# RS232_NPN_PNP_FTDI232.net
KiCad netlist of a schematic drawn in EAGLE
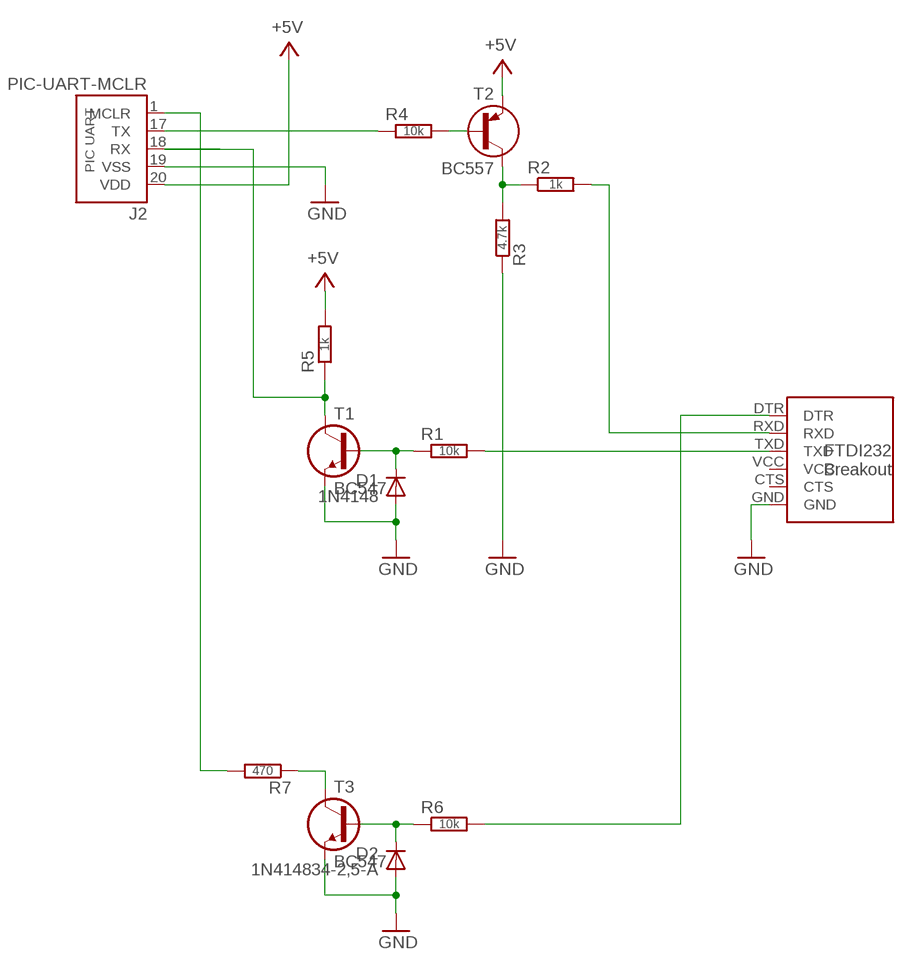
[diagram p0: schematic, sheet 1]

(export (version "E")
  (design (tool "Eeschema 10.0.6"))
  (components
    (comp (ref "D1")
      (value "1N4148")
      (footprint "eagle-import:DO34-5")
      (libsource (lib "eagle-import") (part "1N414834-5"))
    )
    (comp (ref "D2")
      (value "1N414834-2,5-A")
      (footprint "eagle-import:DO34-2,5-A")
      (libsource (lib "eagle-import") (part "1N414834-2,5-A"))
    )
    (comp (ref "J1")
      (value "FTDI232-BO-R")
      (footprint "eagle-import:FTDI232-BO-L")
      (libsource (lib "eagle-import") (part "FTDI232-BO-R"))
    )
    (comp (ref "J2")
      (value "PIC-UART-MCLR")
      (footprint "eagle-import:PIC-UART-MCLR")
      (libsource (lib "eagle-import") (part "PIC-UART-MCLR"))
    )
    (comp (ref "R1")
      (value "10k")
      (footprint "eagle-import:0202_5")
      (libsource (lib "eagle-import") (part "R0202/5"))
    )
    (comp (ref "R2")
      (value "1k")
      (footprint "eagle-import:0202_10")
      (libsource (lib "eagle-import") (part "R0202/10"))
    )
    (comp (ref "R3")
      (value "4.7k")
      (footprint "eagle-import:0202_5")
      (libsource (lib "eagle-import") (part "R0202/5"))
    )
    (comp (ref "R4")
      (value "10k")
      (footprint "eagle-import:0202_7-V")
      (libsource (lib "eagle-import") (part "R0202/7-V"))
    )
    (comp (ref "R5")
      (value "1k")
      (footprint "eagle-import:0202_5-V")
      (libsource (lib "eagle-import") (part "R0202/5-V"))
    )
    (comp (ref "R6")
      (value "10k")
      (footprint "eagle-import:0202_7-V")
      (libsource (lib "eagle-import") (part "R0202/7-V"))
    )
    (comp (ref "R7")
      (value "470")
      (footprint "eagle-import:0202_7-V")
      (libsource (lib "eagle-import") (part "R0202/7-V"))
    )
    (comp (ref "T1")
      (value "BC547")
      (footprint "eagle-import:TO92-CBE")
      (libsource (lib "eagle-import") (part "BC547CBE"))
    )
    (comp (ref "T2")
      (value "BC557")
      (footprint "eagle-import:TO92-CBE")
      (libsource (lib "eagle-import") (part "BC557CBE"))
    )
    (comp (ref "T3")
      (value "BC547")
      (footprint "eagle-import:TO92-CBE")
      (libsource (lib "eagle-import") (part "BC547CBE"))
    )
  )
  (nets
    (net (code "1") (name "+5V") (class "Default")
      (node (ref "J2") (pin "20") (pinfunction "VDD_20") (pintype "passive"))
      (node (ref "R5") (pin "2") (pinfunction "2_2") (pintype "passive"))
      (node (ref "T2") (pin "E") (pinfunction "E_E") (pintype "passive"))
    )
    (net (code "2") (name "GND") (class "Default")
      (node (ref "D1") (pin "A") (pinfunction "A_A") (pintype "passive"))
      (node (ref "D2") (pin "A") (pinfunction "A_A") (pintype "passive"))
      (node (ref "J1") (pin "GND") (pinfunction "GND_GND") (pintype "bidirectional"))
      (node (ref "J2") (pin "19") (pinfunction "VSS_19") (pintype "passive"))
      (node (ref "R3") (pin "1") (pinfunction "1_1") (pintype "passive"))
      (node (ref "T1") (pin "E") (pinfunction "E_E") (pintype "passive"))
      (node (ref "T3") (pin "E") (pinfunction "E_E") (pintype "passive"))
    )
    (net (code "3") (name "Net-(D1-PadC)") (class "Default")
      (node (ref "D1") (pin "C") (pinfunction "C_C") (pintype "passive"))
      (node (ref "R1") (pin "1") (pinfunction "1_1") (pintype "passive"))
      (node (ref "T1") (pin "B") (pinfunction "B_B") (pintype "passive"))
    )
    (net (code "4") (name "Net-(D2-PadC)") (class "Default")
      (node (ref "D2") (pin "C") (pinfunction "C_C") (pintype "passive"))
      (node (ref "R6") (pin "1") (pinfunction "1_1") (pintype "passive"))
      (node (ref "T3") (pin "B") (pinfunction "B_B") (pintype "passive"))
    )
    (net (code "5") (name "Net-(J1-PadDTR)") (class "Default")
      (node (ref "J1") (pin "DTR") (pinfunction "DTR_DTR") (pintype "bidirectional"))
      (node (ref "R6") (pin "2") (pinfunction "2_2") (pintype "passive"))
    )
    (net (code "6") (name "Net-(J1-PadRXD)") (class "Default")
      (node (ref "J1") (pin "RXD") (pinfunction "RXD_RXD") (pintype "bidirectional"))
      (node (ref "R2") (pin "2") (pinfunction "2_2") (pintype "passive"))
    )
    (net (code "7") (name "Net-(J1-PadTXD)") (class "Default")
      (node (ref "J1") (pin "TXD") (pinfunction "TXD_TXD") (pintype "bidirectional"))
      (node (ref "R1") (pin "2") (pinfunction "2_2") (pintype "passive"))
    )
    (net (code "8") (name "Net-(J2-MCLR)") (class "Default")
      (node (ref "J2") (pin "1") (pinfunction "MCLR_1") (pintype "passive"))
      (node (ref "R7") (pin "2") (pinfunction "2_2") (pintype "passive"))
    )
    (net (code "9") (name "Net-(J2-RX)") (class "Default")
      (node (ref "J2") (pin "18") (pinfunction "RX_18") (pintype "passive"))
      (node (ref "R5") (pin "1") (pinfunction "1_1") (pintype "passive"))
      (node (ref "T1") (pin "C") (pinfunction "C_C") (pintype "passive"))
    )
    (net (code "10") (name "Net-(J2-TX)") (class "Default")
      (node (ref "J2") (pin "17") (pinfunction "TX_17") (pintype "passive"))
      (node (ref "R4") (pin "1") (pinfunction "1_1") (pintype "passive"))
    )
    (net (code "11") (name "Net-(R2-Pad1)") (class "Default")
      (node (ref "R2") (pin "1") (pinfunction "1_1") (pintype "passive"))
      (node (ref "R3") (pin "2") (pinfunction "2_2") (pintype "passive"))
      (node (ref "T2") (pin "C") (pinfunction "C_C") (pintype "passive"))
    )
    (net (code "12") (name "Net-(R4-Pad2)") (class "Default")
      (node (ref "R4") (pin "2") (pinfunction "2_2") (pintype "passive"))
      (node (ref "T2") (pin "B") (pinfunction "B_B") (pintype "passive"))
    )
    (net (code "13") (name "Net-(R7-Pad1)") (class "Default")
      (node (ref "R7") (pin "1") (pinfunction "1_1") (pintype "passive"))
      (node (ref "T3") (pin "C") (pinfunction "C_C") (pintype "passive"))
    )
    (net (code "14") (name "unconnected-(J1-PadCTS)") (class "Default")
      (node (ref "J1") (pin "CTS") (pinfunction "CTS_CTS") (pintype "bidirectional"))
    )
    (net (code "15") (name "unconnected-(J1-PadVCC)") (class "Default")
      (node (ref "J1") (pin "VCC") (pinfunction "VCC_VCC") (pintype "bidirectional"))
    )
  )
)
